# STM3205P_VoltageMeasure.net
KiCad netlist of a schematic drawn in Altium Designer
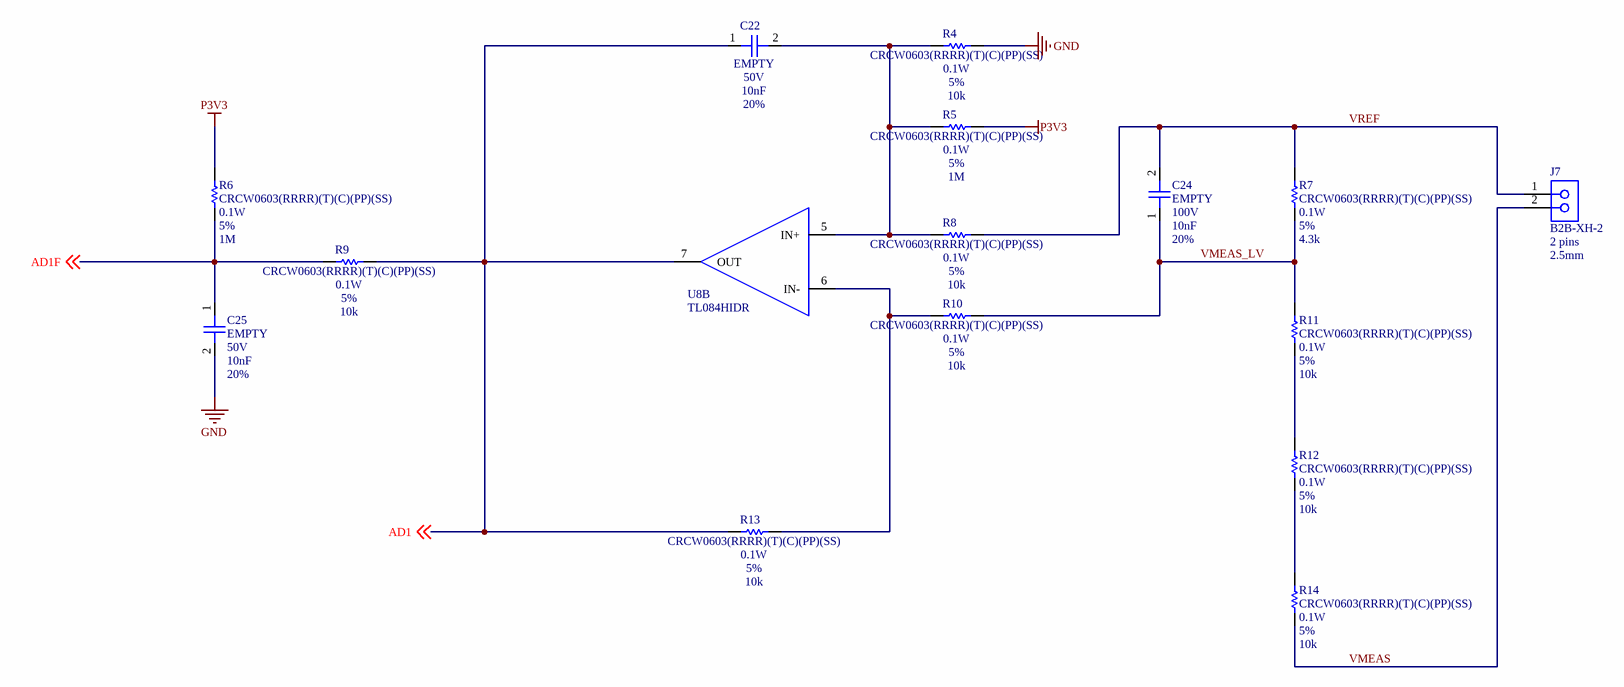
[diagram p0: STM3205P_VoltageMeasure.SchDoc]

(export (version "E")
  (design (tool "Eeschema 10.0.6"))
  (components
    (comp (ref "C22")
      (value "10nF")
      (footprint "CAP0603")
      (description "Surface Mount Multilayer Ceramic Chip Capacitors  for Commercial Applications")
      (fields
        (field (name "PARTNUMBER1") "EMPTY")
        (field (name "VOLTAGE") "50V")
        (field (name "TOLERANCE") "20%")
        (field (name "Comment") "CC0603")
        (field (name "PUBLISHER") "Lucas Moraes")
      )
      (libsource (lib "CeramicCapacitors") (part "CC0603"))
    )
    (comp (ref "C24")
      (value "10nF")
      (footprint "CAP0603")
      (description "Surface Mount Multilayer Ceramic Chip Capacitors  for Commercial Applications")
      (fields
        (field (name "PARTNUMBER1") "EMPTY")
        (field (name "VOLTAGE") "100V")
        (field (name "TOLERANCE") "20%")
        (field (name "Comment") "CC0603")
        (field (name "PUBLISHER") "Lucas Moraes")
      )
      (libsource (lib "CeramicCapacitors") (part "CC0603"))
    )
    (comp (ref "C25")
      (value "10nF")
      (footprint "CAP0603")
      (description "Surface Mount Multilayer Ceramic Chip Capacitors  for Commercial Applications")
      (fields
        (field (name "PARTNUMBER1") "EMPTY")
        (field (name "VOLTAGE") "50V")
        (field (name "TOLERANCE") "20%")
        (field (name "Comment") "CC0603")
        (field (name "PUBLISHER") "Lucas Moraes")
      )
      (libsource (lib "CeramicCapacitors") (part "CC0603"))
    )
    (comp (ref "J7")
      (value "B2B-XH-2")
      (footprint "CONXH02STRMALE_2.5")
      (description "XH Connector 2 POS HDR VERT 2.5mm")
      (fields
        (field (name "PARTNUMBER1") "B2B-XH-2")
        (field (name "PINS") "2 pins")
        (field (name "PITCH") "2.5mm")
        (field (name "PUBLISHER") "Lucas Moraes")
      )
      (libsource (lib "XHConnector") (part "B2B-XH-2"))
    )
    (comp (ref "R4")
      (value "10k")
      (footprint "RES0603")
      (description "Thick Film Chip Resistors with CECC Approval,  available with Established Reliability")
      (fields
        (field (name "PARTNUMBER1") "CRCW0603(RRRR)(T)(C)(PP)(SS)")
        (field (name "POWER") "0.1W")
        (field (name "TOLERANCE") "5%")
        (field (name "Comment") "Chip Resistor")
        (field (name "PUBLISHER") "Lucas Moraes")
      )
      (libsource (lib "ResistorsFixed") (part "CRCW0603"))
    )
    (comp (ref "R5")
      (value "1M")
      (footprint "RES0603")
      (description "Thick Film Chip Resistors with CECC Approval,  available with Established Reliability")
      (fields
        (field (name "PARTNUMBER1") "CRCW0603(RRRR)(T)(C)(PP)(SS)")
        (field (name "POWER") "0.1W")
        (field (name "TOLERANCE") "5%")
        (field (name "Comment") "Chip Resistor")
        (field (name "PUBLISHER") "Lucas Moraes")
      )
      (libsource (lib "ResistorsFixed") (part "CRCW0603"))
    )
    (comp (ref "R6")
      (value "1M")
      (footprint "RES0603")
      (description "Thick Film Chip Resistors with CECC Approval,  available with Established Reliability")
      (fields
        (field (name "PARTNUMBER1") "CRCW0603(RRRR)(T)(C)(PP)(SS)")
        (field (name "POWER") "0.1W")
        (field (name "TOLERANCE") "5%")
        (field (name "Comment") "Chip Resistor")
        (field (name "PUBLISHER") "Lucas Moraes")
      )
      (libsource (lib "ResistorsFixed") (part "CRCW0603"))
    )
    (comp (ref "R7")
      (value "4.3k")
      (footprint "RES0603")
      (description "Thick Film Chip Resistors with CECC Approval,  available with Established Reliability")
      (fields
        (field (name "PARTNUMBER1") "CRCW0603(RRRR)(T)(C)(PP)(SS)")
        (field (name "POWER") "0.1W")
        (field (name "TOLERANCE") "5%")
        (field (name "Comment") "Chip Resistor")
        (field (name "PUBLISHER") "Lucas Moraes")
      )
      (libsource (lib "ResistorsFixed") (part "CRCW0603"))
    )
    (comp (ref "R8")
      (value "10k")
      (footprint "RES0603")
      (description "Thick Film Chip Resistors with CECC Approval,  available with Established Reliability")
      (fields
        (field (name "PARTNUMBER1") "CRCW0603(RRRR)(T)(C)(PP)(SS)")
        (field (name "POWER") "0.1W")
        (field (name "TOLERANCE") "5%")
        (field (name "Comment") "Chip Resistor")
        (field (name "PUBLISHER") "Lucas Moraes")
      )
      (libsource (lib "ResistorsFixed") (part "CRCW0603"))
    )
    (comp (ref "R9")
      (value "10k")
      (footprint "RES0603")
      (description "Thick Film Chip Resistors with CECC Approval,  available with Established Reliability")
      (fields
        (field (name "PARTNUMBER1") "CRCW0603(RRRR)(T)(C)(PP)(SS)")
        (field (name "POWER") "0.1W")
        (field (name "TOLERANCE") "5%")
        (field (name "Comment") "Chip Resistor")
        (field (name "PUBLISHER") "Lucas Moraes")
      )
      (libsource (lib "ResistorsFixed") (part "CRCW0603"))
    )
    (comp (ref "R10")
      (value "10k")
      (footprint "RES0603")
      (description "Thick Film Chip Resistors with CECC Approval,  available with Established Reliability")
      (fields
        (field (name "PARTNUMBER1") "CRCW0603(RRRR)(T)(C)(PP)(SS)")
        (field (name "POWER") "0.1W")
        (field (name "TOLERANCE") "5%")
        (field (name "Comment") "Chip Resistor")
        (field (name "PUBLISHER") "Lucas Moraes")
      )
      (libsource (lib "ResistorsFixed") (part "CRCW0603"))
    )
    (comp (ref "R11")
      (value "10k")
      (footprint "RES0603")
      (description "Thick Film Chip Resistors with CECC Approval,  available with Established Reliability")
      (fields
        (field (name "PARTNUMBER1") "CRCW0603(RRRR)(T)(C)(PP)(SS)")
        (field (name "POWER") "0.1W")
        (field (name "TOLERANCE") "5%")
        (field (name "Comment") "Chip Resistor")
        (field (name "PUBLISHER") "Lucas Moraes")
      )
      (libsource (lib "ResistorsFixed") (part "CRCW0603"))
    )
    (comp (ref "R12")
      (value "10k")
      (footprint "RES0603")
      (description "Thick Film Chip Resistors with CECC Approval,  available with Established Reliability")
      (fields
        (field (name "PARTNUMBER1") "CRCW0603(RRRR)(T)(C)(PP)(SS)")
        (field (name "POWER") "0.1W")
        (field (name "TOLERANCE") "5%")
        (field (name "Comment") "Chip Resistor")
        (field (name "PUBLISHER") "Lucas Moraes")
      )
      (libsource (lib "ResistorsFixed") (part "CRCW0603"))
    )
    (comp (ref "R13")
      (value "10k")
      (footprint "RES0603")
      (description "Thick Film Chip Resistors with CECC Approval,  available with Established Reliability")
      (fields
        (field (name "PARTNUMBER1") "CRCW0603(RRRR)(T)(C)(PP)(SS)")
        (field (name "POWER") "0.1W")
        (field (name "TOLERANCE") "5%")
        (field (name "Comment") "Chip Resistor")
        (field (name "PUBLISHER") "Lucas Moraes")
      )
      (libsource (lib "ResistorsFixed") (part "CRCW0603"))
    )
    (comp (ref "R14")
      (value "10k")
      (footprint "RES0603")
      (description "Thick Film Chip Resistors with CECC Approval,  available with Established Reliability")
      (fields
        (field (name "PARTNUMBER1") "CRCW0603(RRRR)(T)(C)(PP)(SS)")
        (field (name "POWER") "0.1W")
        (field (name "TOLERANCE") "5%")
        (field (name "Comment") "Chip Resistor")
        (field (name "PUBLISHER") "Lucas Moraes")
      )
      (libsource (lib "ResistorsFixed") (part "CRCW0603"))
    )
    (comp (ref "U8")
      (value "TL084HIDR")
      (footprint "SOIC-14-3.9mm")
      (description "Quad Operational Amplifiers RRIO")
      (fields (field (name "PARTNUMBER1") "TL084HIDR") (field (name "PUBLISHER") "Lucas Moraes"))
      (libsource (lib "Amplifiers") (part "TL084HIDR"))
    )
  )
  (nets
    (net (code "1") (name "/VMEAS") (class "Default")
      (node (ref "J7") (pin "2") (pinfunction "2_2") (pintype "passive"))
      (node (ref "R14") (pin "2") (pinfunction "2_2") (pintype "passive"))
    )
    (net (code "2") (name "/VMEAS_LV") (class "Default")
      (node (ref "C24") (pin "1") (pinfunction "1_1") (pintype "passive"))
      (node (ref "R10") (pin "2") (pinfunction "2_2") (pintype "passive"))
      (node (ref "R11") (pin "1") (pinfunction "1_1") (pintype "passive"))
      (node (ref "R7") (pin "2") (pinfunction "2_2") (pintype "passive"))
    )
    (net (code "3") (name "/VREF") (class "Default")
      (node (ref "C24") (pin "2") (pinfunction "2_2") (pintype "passive"))
      (node (ref "J7") (pin "1") (pinfunction "1_1") (pintype "passive"))
      (node (ref "R7") (pin "1") (pinfunction "1_1") (pintype "passive"))
      (node (ref "R8") (pin "2") (pinfunction "2_2") (pintype "passive"))
    )
    (net (code "4") (name "AD1") (class "Default")
      (node (ref "C22") (pin "1") (pinfunction "1_1") (pintype "passive"))
      (node (ref "R13") (pin "1") (pinfunction "1_1") (pintype "passive"))
      (node (ref "R9") (pin "2") (pinfunction "2_2") (pintype "passive"))
      (node (ref "U8") (pin "7") (pinfunction "OUT_7") (pintype "passive"))
    )
    (net (code "5") (name "AD1F") (class "Default")
      (node (ref "C25") (pin "1") (pinfunction "1_1") (pintype "passive"))
      (node (ref "R6") (pin "1") (pinfunction "1_1") (pintype "passive"))
      (node (ref "R9") (pin "1") (pinfunction "1_1") (pintype "passive"))
    )
    (net (code "6") (name "GND") (class "Default")
      (node (ref "C25") (pin "2") (pinfunction "2_2") (pintype "passive"))
      (node (ref "R4") (pin "2") (pinfunction "2_2") (pintype "passive"))
    )
    (net (code "7") (name "Net-(R11-Pad2)") (class "Default")
      (node (ref "R11") (pin "2") (pinfunction "2_2") (pintype "passive"))
      (node (ref "R12") (pin "1") (pinfunction "1_1") (pintype "passive"))
    )
    (net (code "8") (name "Net-(R12-Pad2)") (class "Default")
      (node (ref "R12") (pin "2") (pinfunction "2_2") (pintype "passive"))
      (node (ref "R14") (pin "1") (pinfunction "1_1") (pintype "passive"))
    )
    (net (code "9") (name "Net-(U8B-IN+)") (class "Default")
      (node (ref "C22") (pin "2") (pinfunction "2_2") (pintype "passive"))
      (node (ref "R4") (pin "1") (pinfunction "1_1") (pintype "passive"))
      (node (ref "R5") (pin "1") (pinfunction "1_1") (pintype "passive"))
      (node (ref "R8") (pin "1") (pinfunction "1_1") (pintype "passive"))
      (node (ref "U8") (pin "5") (pinfunction "IN+_5") (pintype "passive"))
    )
    (net (code "10") (name "Net-(U8B-IN-)") (class "Default")
      (node (ref "R10") (pin "1") (pinfunction "1_1") (pintype "passive"))
      (node (ref "R13") (pin "2") (pinfunction "2_2") (pintype "passive"))
      (node (ref "U8") (pin "6") (pinfunction "IN-_6") (pintype "passive"))
    )
    (net (code "11") (name "P3V3") (class "Default")
      (node (ref "R5") (pin "2") (pinfunction "2_2") (pintype "passive"))
      (node (ref "R6") (pin "2") (pinfunction "2_2") (pintype "passive"))
    )
  )
)
